# pcb.net
KiCad netlist of a schematic drawn in EAGLE
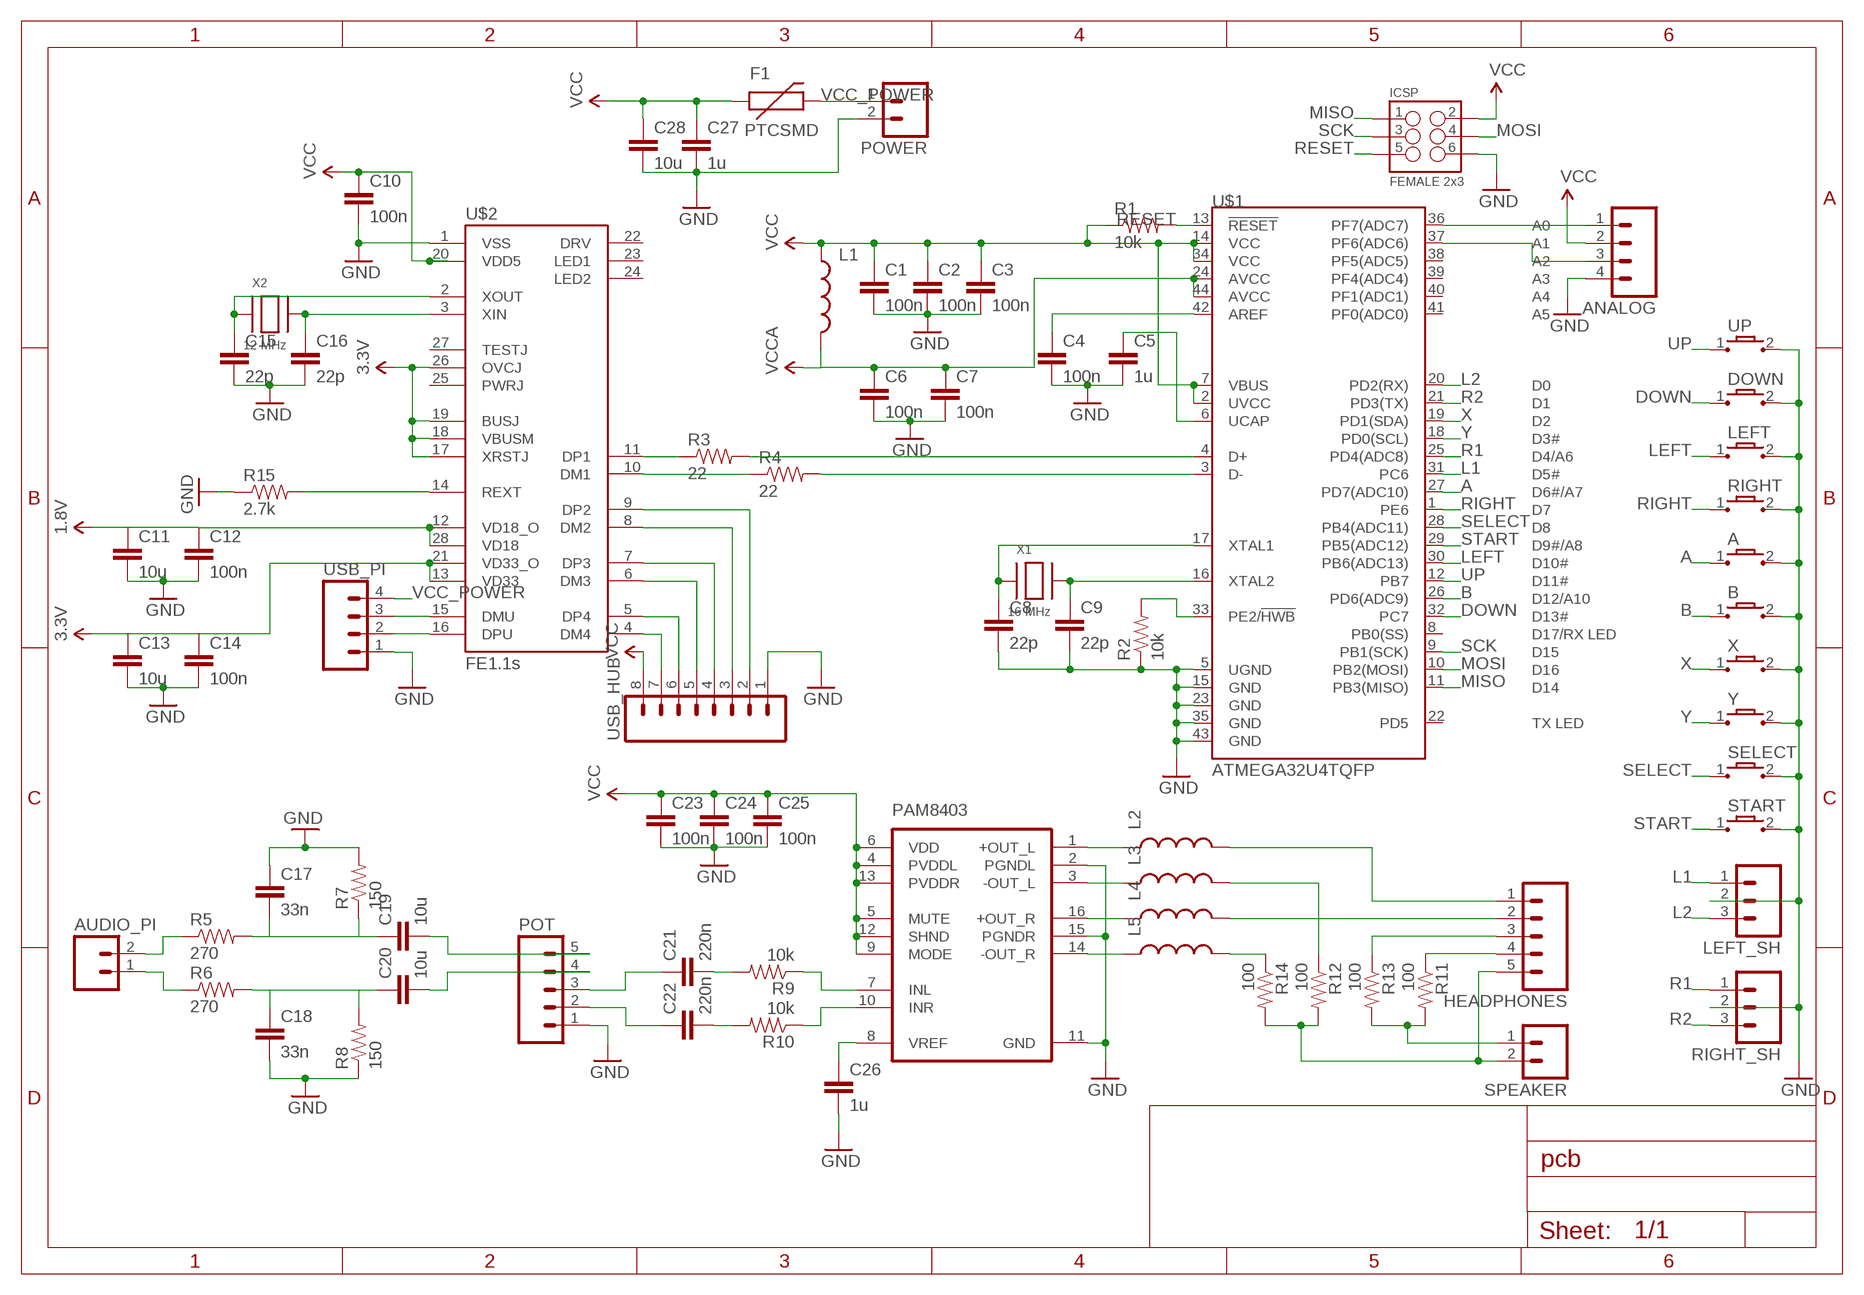
[diagram p0: schematic, sheet 1]

(export (version "E")
  (design (tool "Eeschema 10.0.6"))
  (components
    (comp (ref "A")
      (value "DMG_CONDUCTIVE")
      (footprint "eagle-import:CIRCLE_BUTTON2")
      (libsource (lib "eagle-import") (part "DMG_CONDUCTIVE"))
    )
    (comp (ref "ANALOG")
      (value "M04PTH")
      (footprint "eagle-import:1X04")
      (libsource (lib "eagle-import") (part "M04PTH"))
    )
    (comp (ref "AUDIO_PI")
      (value "M02PTH")
      (footprint "eagle-import:1X02")
      (libsource (lib "eagle-import") (part "M02PTH"))
    )
    (comp (ref "B")
      (value "DMG_CONDUCTIVE")
      (footprint "eagle-import:CIRCLE_BUTTON2")
      (libsource (lib "eagle-import") (part "DMG_CONDUCTIVE"))
    )
    (comp (ref "C1")
      (value "100n")
      (footprint "eagle-import:0805")
      (libsource (lib "eagle-import") (part "CAP0805"))
    )
    (comp (ref "C2")
      (value "100n")
      (footprint "eagle-import:0805")
      (libsource (lib "eagle-import") (part "CAP0805"))
    )
    (comp (ref "C3")
      (value "100n")
      (footprint "eagle-import:0805")
      (libsource (lib "eagle-import") (part "CAP0805"))
    )
    (comp (ref "C4")
      (value "100n")
      (footprint "eagle-import:0805")
      (libsource (lib "eagle-import") (part "CAP0805"))
    )
    (comp (ref "C5")
      (value "1u")
      (footprint "eagle-import:0805")
      (libsource (lib "eagle-import") (part "CAP0805"))
    )
    (comp (ref "C6")
      (value "100n")
      (footprint "eagle-import:0805")
      (libsource (lib "eagle-import") (part "CAP0805"))
    )
    (comp (ref "C7")
      (value "100n")
      (footprint "eagle-import:0805")
      (libsource (lib "eagle-import") (part "CAP0805"))
    )
    (comp (ref "C8")
      (value "22p")
      (footprint "eagle-import:0805")
      (libsource (lib "eagle-import") (part "CAP0805"))
    )
    (comp (ref "C9")
      (value "22p")
      (footprint "eagle-import:0805")
      (libsource (lib "eagle-import") (part "CAP0805"))
    )
    (comp (ref "C10")
      (value "100n")
      (footprint "eagle-import:0805")
      (libsource (lib "eagle-import") (part "CAP0805"))
    )
    (comp (ref "C11")
      (value "10u")
      (footprint "eagle-import:0805")
      (libsource (lib "eagle-import") (part "CAP0805"))
    )
    (comp (ref "C12")
      (value "100n")
      (footprint "eagle-import:0805")
      (libsource (lib "eagle-import") (part "CAP0805"))
    )
    (comp (ref "C13")
      (value "10u")
      (footprint "eagle-import:0805")
      (libsource (lib "eagle-import") (part "CAP0805"))
    )
    (comp (ref "C14")
      (value "100n")
      (footprint "eagle-import:0805")
      (libsource (lib "eagle-import") (part "CAP0805"))
    )
    (comp (ref "C15")
      (value "22p")
      (footprint "eagle-import:0805")
      (libsource (lib "eagle-import") (part "CAP0805"))
    )
    (comp (ref "C16")
      (value "22p")
      (footprint "eagle-import:0805")
      (libsource (lib "eagle-import") (part "CAP0805"))
    )
    (comp (ref "C17")
      (value "33n")
      (footprint "eagle-import:0805")
      (libsource (lib "eagle-import") (part "CAP0805"))
    )
    (comp (ref "C18")
      (value "33n")
      (footprint "eagle-import:0805")
      (libsource (lib "eagle-import") (part "CAP0805"))
    )
    (comp (ref "C19")
      (value "10u")
      (footprint "eagle-import:0805")
      (libsource (lib "eagle-import") (part "CAP0805"))
    )
    (comp (ref "C20")
      (value "10u")
      (footprint "eagle-import:0805")
      (libsource (lib "eagle-import") (part "CAP0805"))
    )
    (comp (ref "C21")
      (value "220n")
      (footprint "eagle-import:0805")
      (libsource (lib "eagle-import") (part "CAP0805"))
    )
    (comp (ref "C22")
      (value "220n")
      (footprint "eagle-import:0805")
      (libsource (lib "eagle-import") (part "CAP0805"))
    )
    (comp (ref "C23")
      (value "100n")
      (footprint "eagle-import:0805")
      (libsource (lib "eagle-import") (part "CAP0805"))
    )
    (comp (ref "C24")
      (value "100n")
      (footprint "eagle-import:0805")
      (libsource (lib "eagle-import") (part "CAP0805"))
    )
    (comp (ref "C25")
      (value "100n")
      (footprint "eagle-import:0805")
      (libsource (lib "eagle-import") (part "CAP0805"))
    )
    (comp (ref "C26")
      (value "1u")
      (footprint "eagle-import:0805")
      (libsource (lib "eagle-import") (part "CAP0805"))
    )
    (comp (ref "C27")
      (value "1u")
      (footprint "eagle-import:0805")
      (libsource (lib "eagle-import") (part "CAP0805"))
    )
    (comp (ref "C28")
      (value "10u")
      (footprint "eagle-import:0805")
      (libsource (lib "eagle-import") (part "CAP0805"))
    )
    (comp (ref "DOWN")
      (value "DMG_CONDUCTIVE")
      (footprint "eagle-import:CIRCLE_BUTTON2")
      (libsource (lib "eagle-import") (part "DMG_CONDUCTIVE"))
    )
    (comp (ref "F1")
      (value "PTCSMD")
      (footprint "eagle-import:PTC-1206")
      (libsource (lib "eagle-import") (part "PTCSMD"))
    )
    (comp (ref "HEADPHONES")
      (value "M05PTH")
      (footprint "eagle-import:1X05")
      (libsource (lib "eagle-import") (part "M05PTH"))
    )
    (comp (ref "ICSP")
      (value "FEMALE 2x3")
      (footprint "eagle-import:2X3")
      (libsource (lib "eagle-import") (part "M03X2FEMALE"))
    )
    (comp (ref "L1")
      (value "INDUCTOR0805")
      (footprint "eagle-import:0805")
      (libsource (lib "eagle-import") (part "INDUCTOR0805"))
    )
    (comp (ref "L2")
      (value "INDUCTOR0805")
      (footprint "eagle-import:0805")
      (libsource (lib "eagle-import") (part "INDUCTOR0805"))
    )
    (comp (ref "L3")
      (value "INDUCTOR0805")
      (footprint "eagle-import:0805")
      (libsource (lib "eagle-import") (part "INDUCTOR0805"))
    )
    (comp (ref "L4")
      (value "INDUCTOR0805")
      (footprint "eagle-import:0805")
      (libsource (lib "eagle-import") (part "INDUCTOR0805"))
    )
    (comp (ref "L5")
      (value "INDUCTOR0805")
      (footprint "eagle-import:0805")
      (libsource (lib "eagle-import") (part "INDUCTOR0805"))
    )
    (comp (ref "LEFT")
      (value "DMG_CONDUCTIVE")
      (footprint "eagle-import:CIRCLE_BUTTON2")
      (libsource (lib "eagle-import") (part "DMG_CONDUCTIVE"))
    )
    (comp (ref "LEFT_SH")
      (value "M03PTH")
      (footprint "eagle-import:1X03")
      (libsource (lib "eagle-import") (part "M03PTH"))
    )
    (comp (ref "PAM8403")
      (value "PAM8403")
      (footprint "eagle-import:SOP-16")
      (libsource (lib "eagle-import") (part "PAM8403"))
    )
    (comp (ref "POT")
      (value "M05PTH")
      (footprint "eagle-import:1X05")
      (libsource (lib "eagle-import") (part "M05PTH"))
    )
    (comp (ref "POWER")
      (value "M02PTH")
      (footprint "eagle-import:1X02")
      (libsource (lib "eagle-import") (part "M02PTH"))
    )
    (comp (ref "R1")
      (value "10k")
      (footprint "eagle-import:0805")
      (libsource (lib "eagle-import") (part "RESISTOR0805-RES"))
    )
    (comp (ref "R2")
      (value "10k")
      (footprint "eagle-import:0805")
      (libsource (lib "eagle-import") (part "RESISTOR0805-RES"))
    )
    (comp (ref "R3")
      (value "22")
      (footprint "eagle-import:0805")
      (libsource (lib "eagle-import") (part "RESISTOR0805-RES"))
    )
    (comp (ref "R4")
      (value "22")
      (footprint "eagle-import:0805")
      (libsource (lib "eagle-import") (part "RESISTOR0805-RES"))
    )
    (comp (ref "R5")
      (value "270")
      (footprint "eagle-import:0805")
      (libsource (lib "eagle-import") (part "RESISTOR0805-RES"))
    )
    (comp (ref "R6")
      (value "270")
      (footprint "eagle-import:0805")
      (libsource (lib "eagle-import") (part "RESISTOR0805-RES"))
    )
    (comp (ref "R7")
      (value "150")
      (footprint "eagle-import:0805")
      (libsource (lib "eagle-import") (part "RESISTOR0805-RES"))
    )
    (comp (ref "R8")
      (value "150")
      (footprint "eagle-import:0805")
      (libsource (lib "eagle-import") (part "RESISTOR0805-RES"))
    )
    (comp (ref "R9")
      (value "10k")
      (footprint "eagle-import:0805")
      (libsource (lib "eagle-import") (part "RESISTOR0805-RES"))
    )
    (comp (ref "R10")
      (value "10k")
      (footprint "eagle-import:0805")
      (libsource (lib "eagle-import") (part "RESISTOR0805-RES"))
    )
    (comp (ref "R11")
      (value "100")
      (footprint "eagle-import:0805")
      (libsource (lib "eagle-import") (part "RESISTOR0805-RES"))
    )
    (comp (ref "R12")
      (value "100")
      (footprint "eagle-import:0805")
      (libsource (lib "eagle-import") (part "RESISTOR0805-RES"))
    )
    (comp (ref "R13")
      (value "100")
      (footprint "eagle-import:0805")
      (libsource (lib "eagle-import") (part "RESISTOR0805-RES"))
    )
    (comp (ref "R14")
      (value "100")
      (footprint "eagle-import:0805")
      (libsource (lib "eagle-import") (part "RESISTOR0805-RES"))
    )
    (comp (ref "R15")
      (value "2.7k")
      (footprint "eagle-import:0805")
      (libsource (lib "eagle-import") (part "RESISTOR0805-RES"))
    )
    (comp (ref "RIGHT")
      (value "DMG_CONDUCTIVE")
      (footprint "eagle-import:CIRCLE_BUTTON2")
      (libsource (lib "eagle-import") (part "DMG_CONDUCTIVE"))
    )
    (comp (ref "RIGHT_SH")
      (value "M03PTH")
      (footprint "eagle-import:1X03")
      (libsource (lib "eagle-import") (part "M03PTH"))
    )
    (comp (ref "SELECT")
      (value "DMG_CONDUCTIVE2")
      (footprint "eagle-import:START_STOP2")
      (libsource (lib "eagle-import") (part "DMG_CONDUCTIVE2"))
    )
    (comp (ref "SPEAKER")
      (value "M02PTH")
      (footprint "eagle-import:1X02")
      (libsource (lib "eagle-import") (part "M02PTH"))
    )
    (comp (ref "START")
      (value "DMG_CONDUCTIVE2")
      (footprint "eagle-import:START_STOP2")
      (libsource (lib "eagle-import") (part "DMG_CONDUCTIVE2"))
    )
    (comp (ref "U$1")
      (value "ATMEGA32U4TQFP")
      (footprint "eagle-import:SPARKFUN-DIGITALIC_TQFP44")
      (libsource (lib "eagle-import") (part "ATMEGA32U4TQFP"))
    )
    (comp (ref "U$2")
      (value "FE1.1S")
      (footprint "eagle-import:FE1.1S_SSOP-28")
      (libsource (lib "eagle-import") (part "FE1.1S"))
    )
    (comp (ref "UP")
      (value "DMG_CONDUCTIVE")
      (footprint "eagle-import:CIRCLE_BUTTON2")
      (libsource (lib "eagle-import") (part "DMG_CONDUCTIVE"))
    )
    (comp (ref "USB_HUB")
      (value "M08")
      (footprint "eagle-import:1X08_ROUND")
      (libsource (lib "eagle-import") (part "M08"))
    )
    (comp (ref "USB_PI")
      (value "M04PTH")
      (footprint "eagle-import:1X04")
      (libsource (lib "eagle-import") (part "M04PTH"))
    )
    (comp (ref "X")
      (value "DMG_CONDUCTIVE")
      (footprint "eagle-import:CIRCLE_BUTTON2")
      (libsource (lib "eagle-import") (part "DMG_CONDUCTIVE"))
    )
    (comp (ref "X1")
      (value "16 MHz")
      (footprint "eagle-import:NX5032")
      (libsource (lib "eagle-import") (part "XTALNX5032"))
    )
    (comp (ref "X2")
      (value "12 MHz")
      (footprint "eagle-import:NX5032")
      (libsource (lib "eagle-import") (part "XTALNX5032"))
    )
    (comp (ref "Y")
      (value "DMG_CONDUCTIVE")
      (footprint "eagle-import:CIRCLE_BUTTON2")
      (libsource (lib "eagle-import") (part "DMG_CONDUCTIVE"))
    )
  )
  (nets
    (net (code "1") (name "/A") (class "Default")
      (node (ref "A") (pin "1") (pinfunction "1_1") (pintype "passive"))
      (node (ref "U$1") (pin "27") (pinfunction "PD7(ADC10)_27") (pintype "bidirectional"))
    )
    (net (code "2") (name "/B") (class "Default")
      (node (ref "B") (pin "1") (pinfunction "1_1") (pintype "passive"))
      (node (ref "U$1") (pin "26") (pinfunction "PD6(ADC9)_26") (pintype "bidirectional"))
    )
    (net (code "3") (name "/DOWN") (class "Default")
      (node (ref "DOWN") (pin "1") (pinfunction "1_1") (pintype "passive"))
      (node (ref "U$1") (pin "32") (pinfunction "PC7_32") (pintype "bidirectional"))
    )
    (net (code "4") (name "/L1") (class "Default")
      (node (ref "LEFT_SH") (pin "1") (pinfunction "1_1") (pintype "passive"))
      (node (ref "U$1") (pin "31") (pinfunction "PC6_31") (pintype "bidirectional"))
    )
    (net (code "5") (name "/L2") (class "Default")
      (node (ref "LEFT_SH") (pin "3") (pinfunction "3_3") (pintype "passive"))
      (node (ref "U$1") (pin "20") (pinfunction "PD2(RX)_20") (pintype "bidirectional"))
    )
    (net (code "6") (name "/LEFT") (class "Default")
      (node (ref "LEFT") (pin "1") (pinfunction "1_1") (pintype "passive"))
      (node (ref "U$1") (pin "30") (pinfunction "PB6(ADC13)_30") (pintype "bidirectional"))
    )
    (net (code "7") (name "/MISO") (class "Default")
      (node (ref "ICSP") (pin "1") (pinfunction "1_1") (pintype "bidirectional"))
      (node (ref "U$1") (pin "11") (pinfunction "PB3(MISO)_11") (pintype "bidirectional"))
    )
    (net (code "8") (name "/MOSI") (class "Default")
      (node (ref "ICSP") (pin "4") (pinfunction "4_4") (pintype "bidirectional"))
      (node (ref "U$1") (pin "10") (pinfunction "PB2(MOSI)_10") (pintype "bidirectional"))
    )
    (net (code "9") (name "/R1") (class "Default")
      (node (ref "RIGHT_SH") (pin "1") (pinfunction "1_1") (pintype "passive"))
      (node (ref "U$1") (pin "25") (pinfunction "PD4(ADC8)_25") (pintype "bidirectional"))
    )
    (net (code "10") (name "/R2") (class "Default")
      (node (ref "RIGHT_SH") (pin "3") (pinfunction "3_3") (pintype "passive"))
      (node (ref "U$1") (pin "21") (pinfunction "PD3(TX)_21") (pintype "bidirectional"))
    )
    (net (code "11") (name "/RESET") (class "Default")
      (node (ref "ICSP") (pin "5") (pinfunction "5_5") (pintype "bidirectional"))
      (node (ref "R1") (pin "2") (pinfunction "2_2") (pintype "passive"))
      (node (ref "U$1") (pin "13") (pinfunction "~{RESET}_13") (pintype "bidirectional"))
    )
    (net (code "12") (name "/RIGHT") (class "Default")
      (node (ref "RIGHT") (pin "1") (pinfunction "1_1") (pintype "passive"))
      (node (ref "U$1") (pin "1") (pinfunction "PE6_1") (pintype "bidirectional"))
    )
    (net (code "13") (name "/SCK") (class "Default")
      (node (ref "ICSP") (pin "3") (pinfunction "3_3") (pintype "bidirectional"))
      (node (ref "U$1") (pin "9") (pinfunction "PB1(SCK)_9") (pintype "bidirectional"))
    )
    (net (code "14") (name "/SELECT") (class "Default")
      (node (ref "SELECT") (pin "1") (pinfunction "1_1") (pintype "passive"))
      (node (ref "U$1") (pin "28") (pinfunction "PB4(ADC11)_28") (pintype "bidirectional"))
    )
    (net (code "15") (name "/START") (class "Default")
      (node (ref "START") (pin "1") (pinfunction "1_1") (pintype "passive"))
      (node (ref "U$1") (pin "29") (pinfunction "PB5(ADC12)_29") (pintype "bidirectional"))
    )
    (net (code "16") (name "/UP") (class "Default")
      (node (ref "U$1") (pin "12") (pinfunction "PB7_12") (pintype "bidirectional"))
      (node (ref "UP") (pin "1") (pinfunction "1_1") (pintype "passive"))
    )
    (net (code "17") (name "/VCC_POWER") (class "Default")
      (node (ref "F1") (pin "2") (pinfunction "2_2") (pintype "bidirectional"))
      (node (ref "POWER") (pin "1") (pinfunction "1_1") (pintype "passive"))
      (node (ref "USB_PI") (pin "4") (pinfunction "4_4") (pintype "passive"))
    )
    (net (code "18") (name "/X") (class "Default")
      (node (ref "U$1") (pin "19") (pinfunction "PD1(SDA)_19") (pintype "bidirectional"))
      (node (ref "X") (pin "1") (pinfunction "1_1") (pintype "passive"))
    )
    (net (code "19") (name "/Y") (class "Default")
      (node (ref "U$1") (pin "18") (pinfunction "PD0(SCL)_18") (pintype "bidirectional"))
      (node (ref "Y") (pin "1") (pinfunction "1_1") (pintype "passive"))
    )
    (net (code "20") (name "1.8V") (class "Default")
      (node (ref "C11") (pin "1") (pinfunction "1_1") (pintype "passive"))
      (node (ref "C12") (pin "1") (pinfunction "1_1") (pintype "passive"))
      (node (ref "U$2") (pin "12") (pinfunction "VD18_O_12") (pintype "bidirectional"))
      (node (ref "U$2") (pin "28") (pinfunction "VD18_28") (pintype "bidirectional"))
    )
    (net (code "21") (name "3.3V") (class "Default")
      (node (ref "C13") (pin "1") (pinfunction "1_1") (pintype "passive"))
      (node (ref "C14") (pin "1") (pinfunction "1_1") (pintype "passive"))
      (node (ref "U$2") (pin "13") (pinfunction "VD33_13") (pintype "bidirectional"))
      (node (ref "U$2") (pin "17") (pinfunction "XRSTJ_17") (pintype "bidirectional"))
      (node (ref "U$2") (pin "18") (pinfunction "VBUSM_18") (pintype "bidirectional"))
      (node (ref "U$2") (pin "19") (pinfunction "BUSJ_19") (pintype "bidirectional"))
      (node (ref "U$2") (pin "21") (pinfunction "VD33_O_21") (pintype "bidirectional"))
      (node (ref "U$2") (pin "26") (pinfunction "OVCJ_26") (pintype "bidirectional"))
    )
    (net (code "22") (name "GND") (class "Default")
      (node (ref "A") (pin "2") (pinfunction "2_2") (pintype "passive"))
      (node (ref "ANALOG") (pin "4") (pinfunction "4_4") (pintype "passive"))
      (node (ref "B") (pin "2") (pinfunction "2_2") (pintype "passive"))
      (node (ref "C1") (pin "2") (pinfunction "2_2") (pintype "passive"))
      (node (ref "C10") (pin "2") (pinfunction "2_2") (pintype "passive"))
      (node (ref "C11") (pin "2") (pinfunction "2_2") (pintype "passive"))
      (node (ref "C12") (pin "2") (pinfunction "2_2") (pintype "passive"))
      (node (ref "C13") (pin "2") (pinfunction "2_2") (pintype "passive"))
      (node (ref "C14") (pin "2") (pinfunction "2_2") (pintype "passive"))
      (node (ref "C15") (pin "2") (pinfunction "2_2") (pintype "passive"))
      (node (ref "C16") (pin "2") (pinfunction "2_2") (pintype "passive"))
      (node (ref "C17") (pin "1") (pinfunction "1_1") (pintype "passive"))
      (node (ref "C18") (pin "2") (pinfunction "2_2") (pintype "passive"))
      (node (ref "C2") (pin "2") (pinfunction "2_2") (pintype "passive"))
      (node (ref "C23") (pin "2") (pinfunction "2_2") (pintype "passive"))
      (node (ref "C24") (pin "2") (pinfunction "2_2") (pintype "passive"))
      (node (ref "C25") (pin "2") (pinfunction "2_2") (pintype "passive"))
      (node (ref "C26") (pin "2") (pinfunction "2_2") (pintype "passive"))
      (node (ref "C27") (pin "2") (pinfunction "2_2") (pintype "passive"))
      (node (ref "C28") (pin "2") (pinfunction "2_2") (pintype "passive"))
      (node (ref "C3") (pin "2") (pinfunction "2_2") (pintype "passive"))
      (node (ref "C4") (pin "2") (pinfunction "2_2") (pintype "passive"))
      (node (ref "C5") (pin "2") (pinfunction "2_2") (pintype "passive"))
      (node (ref "C6") (pin "2") (pinfunction "2_2") (pintype "passive"))
      (node (ref "C7") (pin "2") (pinfunction "2_2") (pintype "passive"))
      (node (ref "C8") (pin "2") (pinfunction "2_2") (pintype "passive"))
      (node (ref "C9") (pin "2") (pinfunction "2_2") (pintype "passive"))
      (node (ref "DOWN") (pin "2") (pinfunction "2_2") (pintype "passive"))
      (node (ref "ICSP") (pin "6") (pinfunction "6_6") (pintype "bidirectional"))
      (node (ref "LEFT") (pin "2") (pinfunction "2_2") (pintype "passive"))
      (node (ref "LEFT_SH") (pin "2") (pinfunction "2_2") (pintype "passive"))
      (node (ref "PAM8403") (pin "11") (pinfunction "GND_11") (pintype "output"))
      (node (ref "PAM8403") (pin "15") (pinfunction "PGNDR_15") (pintype "output"))
      (node (ref "PAM8403") (pin "2") (pinfunction "PGNDL_2") (pintype "input"))
      (node (ref "POT") (pin "1") (pinfunction "1_1") (pintype "passive"))
      (node (ref "POWER") (pin "2") (pinfunction "2_2") (pintype "passive"))
      (node (ref "R15") (pin "1") (pinfunction "1_1") (pintype "passive"))
      (node (ref "R2") (pin "1") (pinfunction "1_1") (pintype "passive"))
      (node (ref "R7") (pin "2") (pinfunction "2_2") (pintype "passive"))
      (node (ref "R8") (pin "1") (pinfunction "1_1") (pintype "passive"))
      (node (ref "RIGHT") (pin "2") (pinfunction "2_2") (pintype "passive"))
      (node (ref "RIGHT_SH") (pin "2") (pinfunction "2_2") (pintype "passive"))
      (node (ref "SELECT") (pin "2") (pinfunction "2_2") (pintype "passive"))
      (node (ref "START") (pin "2") (pinfunction "2_2") (pintype "passive"))
      (node (ref "U$1") (pin "15") (pinfunction "GND_15") (pintype "bidirectional"))
      (node (ref "U$1") (pin "23") (pinfunction "GND_23") (pintype "bidirectional"))
      (node (ref "U$1") (pin "35") (pinfunction "GND_35") (pintype "bidirectional"))
      (node (ref "U$1") (pin "43") (pinfunction "GND_43") (pintype "bidirectional"))
      (node (ref "U$1") (pin "5") (pinfunction "UGND_5") (pintype "bidirectional"))
      (node (ref "U$2") (pin "1") (pinfunction "VSS_1") (pintype "bidirectional"))
      (node (ref "UP") (pin "2") (pinfunction "2_2") (pintype "passive"))
      (node (ref "USB_HUB") (pin "1") (pinfunction "1_1") (pintype "passive"))
      (node (ref "USB_PI") (pin "1") (pinfunction "1_1") (pintype "passive"))
      (node (ref "X") (pin "2") (pinfunction "2_2") (pintype "passive"))
      (node (ref "Y") (pin "2") (pinfunction "2_2") (pintype "passive"))
    )
    (net (code "23") (name "Net-(AUDIO_PI-Pad1)") (class "Default")
      (node (ref "AUDIO_PI") (pin "1") (pinfunction "1_1") (pintype "passive"))
      (node (ref "R6") (pin "1") (pinfunction "1_1") (pintype "passive"))
    )
    (net (code "24") (name "Net-(AUDIO_PI-Pad2)") (class "Default")
      (node (ref "AUDIO_PI") (pin "2") (pinfunction "2_2") (pintype "passive"))
      (node (ref "R5") (pin "1") (pinfunction "1_1") (pintype "passive"))
    )
    (net (code "25") (name "Net-(C17-Pad2)") (class "Default")
      (node (ref "C17") (pin "2") (pinfunction "2_2") (pintype "passive"))
      (node (ref "C19") (pin "1") (pinfunction "1_1") (pintype "passive"))
      (node (ref "R5") (pin "2") (pinfunction "2_2") (pintype "passive"))
      (node (ref "R7") (pin "1") (pinfunction "1_1") (pintype "passive"))
    )
    (net (code "26") (name "Net-(C18-Pad1)") (class "Default")
      (node (ref "C18") (pin "1") (pinfunction "1_1") (pintype "passive"))
      (node (ref "C20") (pin "1") (pinfunction "1_1") (pintype "passive"))
      (node (ref "R6") (pin "2") (pinfunction "2_2") (pintype "passive"))
      (node (ref "R8") (pin "2") (pinfunction "2_2") (pintype "passive"))
    )
    (net (code "27") (name "Net-(C19-Pad2)") (class "Default")
      (node (ref "C19") (pin "2") (pinfunction "2_2") (pintype "passive"))
      (node (ref "POT") (pin "5") (pinfunction "5_5") (pintype "passive"))
    )
    (net (code "28") (name "Net-(C20-Pad2)") (class "Default")
      (node (ref "C20") (pin "2") (pinfunction "2_2") (pintype "passive"))
      (node (ref "POT") (pin "4") (pinfunction "4_4") (pintype "passive"))
    )
    (net (code "29") (name "Net-(C21-Pad1)") (class "Default")
      (node (ref "C21") (pin "1") (pinfunction "1_1") (pintype "passive"))
      (node (ref "POT") (pin "3") (pinfunction "3_3") (pintype "passive"))
    )
    (net (code "30") (name "Net-(C21-Pad2)") (class "Default")
      (node (ref "C21") (pin "2") (pinfunction "2_2") (pintype "passive"))
      (node (ref "R9") (pin "2") (pinfunction "2_2") (pintype "passive"))
    )
    (net (code "31") (name "Net-(C22-Pad1)") (class "Default")
      (node (ref "C22") (pin "1") (pinfunction "1_1") (pintype "passive"))
      (node (ref "POT") (pin "2") (pinfunction "2_2") (pintype "passive"))
    )
    (net (code "32") (name "Net-(C22-Pad2)") (class "Default")
      (node (ref "C22") (pin "2") (pinfunction "2_2") (pintype "passive"))
      (node (ref "R10") (pin "2") (pinfunction "2_2") (pintype "passive"))
    )
    (net (code "33") (name "Net-(HEADPHONES-Pad1)") (class "Default")
      (node (ref "HEADPHONES") (pin "1") (pinfunction "1_1") (pintype "passive"))
      (node (ref "L2") (pin "2") (pinfunction "2_2") (pintype "passive"))
    )
    (net (code "34") (name "Net-(HEADPHONES-Pad2)") (class "Default")
      (node (ref "HEADPHONES") (pin "2") (pinfunction "2_2") (pintype "passive"))
      (node (ref "L4") (pin "2") (pinfunction "2_2") (pintype "passive"))
    )
    (net (code "35") (name "Net-(HEADPHONES-Pad3)") (class "Default")
      (node (ref "HEADPHONES") (pin "3") (pinfunction "3_3") (pintype "passive"))
      (node (ref "R13") (pin "1") (pinfunction "1_1") (pintype "passive"))
    )
    (net (code "36") (name "Net-(HEADPHONES-Pad4)") (class "Default")
      (node (ref "HEADPHONES") (pin "4") (pinfunction "4_4") (pintype "passive"))
      (node (ref "R11") (pin "1") (pinfunction "1_1") (pintype "passive"))
    )
    (net (code "37") (name "Net-(HEADPHONES-Pad5)") (class "Default")
      (node (ref "HEADPHONES") (pin "5") (pinfunction "5_5") (pintype "passive"))
      (node (ref "R12") (pin "2") (pinfunction "2_2") (pintype "passive"))
      (node (ref "R14") (pin "2") (pinfunction "2_2") (pintype "passive"))
      (node (ref "SPEAKER") (pin "2") (pinfunction "2_2") (pintype "passive"))
    )
    (net (code "38") (name "Net-(L3-Pad2)") (class "Default")
      (node (ref "L3") (pin "2") (pinfunction "2_2") (pintype "passive"))
      (node (ref "R12") (pin "1") (pinfunction "1_1") (pintype "passive"))
    )
    (net (code "39") (name "Net-(L5-Pad2)") (class "Default")
      (node (ref "L5") (pin "2") (pinfunction "2_2") (pintype "passive"))
      (node (ref "R14") (pin "1") (pinfunction "1_1") (pintype "passive"))
    )
    (net (code "40") (name "Net-(PAM8403-+OUT_L)") (class "Default")
      (node (ref "L2") (pin "1") (pinfunction "1_1") (pintype "passive"))
      (node (ref "PAM8403") (pin "1") (pinfunction "+OUT_L_1") (pintype "input"))
    )
    (net (code "41") (name "Net-(PAM8403-+OUT_R)") (class "Default")
      (node (ref "L4") (pin "1") (pinfunction "1_1") (pintype "passive"))
      (node (ref "PAM8403") (pin "16") (pinfunction "+OUT_R_16") (pintype "output"))
    )
    (net (code "42") (name "Net-(PAM8403--OUT_L)") (class "Default")
      (node (ref "L3") (pin "1") (pinfunction "1_1") (pintype "passive"))
      (node (ref "PAM8403") (pin "3") (pinfunction "-OUT_L_3") (pintype "input"))
    )
    (net (code "43") (name "Net-(PAM8403--OUT_R)") (class "Default")
      (node (ref "L5") (pin "1") (pinfunction "1_1") (pintype "passive"))
      (node (ref "PAM8403") (pin "14") (pinfunction "-OUT_R_14") (pintype "output"))
    )
    (net (code "44") (name "Net-(PAM8403-INL)") (class "Default")
      (node (ref "PAM8403") (pin "7") (pinfunction "INL_7") (pintype "input"))
      (node (ref "R9") (pin "1") (pinfunction "1_1") (pintype "passive"))
    )
    (net (code "45") (name "Net-(PAM8403-INR)") (class "Default")
      (node (ref "PAM8403") (pin "10") (pinfunction "INR_10") (pintype "output"))
      (node (ref "R10") (pin "1") (pinfunction "1_1") (pintype "passive"))
    )
    (net (code "46") (name "Net-(PAM8403-VREF)") (class "Default")
      (node (ref "C26") (pin "1") (pinfunction "1_1") (pintype "passive"))
      (node (ref "PAM8403") (pin "8") (pinfunction "VREF_8") (pintype "input"))
    )
    (net (code "47") (name "Net-(R11-Pad2)") (class "Default")
      (node (ref "R11") (pin "2") (pinfunction "2_2") (pintype "passive"))
      (node (ref "R13") (pin "2") (pinfunction "2_2") (pintype "passive"))
      (node (ref "SPEAKER") (pin "1") (pinfunction "1_1") (pintype "passive"))
    )
    (net (code "48") (name "Net-(U$1-AREF)") (class "Default")
      (node (ref "C4") (pin "1") (pinfunction "1_1") (pintype "passive"))
      (node (ref "U$1") (pin "42") (pinfunction "AREF_42") (pintype "bidirectional"))
    )
    (net (code "49") (name "Net-(U$1-D+)") (class "Default")
      (node (ref "R3") (pin "2") (pinfunction "2_2") (pintype "passive"))
      (node (ref "U$1") (pin "4") (pinfunction "D+_4") (pintype "bidirectional"))
    )
    (net (code "50") (name "Net-(U$1-D-)") (class "Default")
      (node (ref "R4") (pin "2") (pinfunction "2_2") (pintype "passive"))
      (node (ref "U$1") (pin "3") (pinfunction "D-_3") (pintype "bidirectional"))
    )
    (net (code "51") (name "Net-(U$1-PE2{slash}~{HWB})") (class "Default")
      (node (ref "R2") (pin "2") (pinfunction "2_2") (pintype "passive"))
      (node (ref "U$1") (pin "33") (pinfunction "PE2/~{HWB}_33") (pintype "bidirectional"))
    )
    (net (code "52") (name "Net-(U$1-PF6(ADC6))") (class "Default")
      (node (ref "ANALOG") (pin "3") (pinfunction "3_3") (pintype "passive"))
      (node (ref "U$1") (pin "37") (pinfunction "PF6(ADC6)_37") (pintype "bidirectional"))
    )
    (net (code "53") (name "Net-(U$1-PF7(ADC7))") (class "Default")
      (node (ref "ANALOG") (pin "1") (pinfunction "1_1") (pintype "passive"))
      (node (ref "U$1") (pin "36") (pinfunction "PF7(ADC7)_36") (pintype "bidirectional"))
    )
    (net (code "54") (name "Net-(U$1-UCAP)") (class "Default")
      (node (ref "C5") (pin "1") (pinfunction "1_1") (pintype "passive"))
      (node (ref "U$1") (pin "6") (pinfunction "UCAP_6") (pintype "bidirectional"))
    )
    (net (code "55") (name "Net-(U$1-XTAL1)") (class "Default")
      (node (ref "C8") (pin "1") (pinfunction "1_1") (pintype "passive"))
      (node (ref "U$1") (pin "17") (pinfunction "XTAL1_17") (pintype "bidirectional"))
      (node (ref "X1") (pin "P$1") (pinfunction "P$1_P$1") (pintype "bidirectional"))
    )
    (net (code "56") (name "Net-(U$1-XTAL2)") (class "Default")
      (node (ref "C9") (pin "1") (pinfunction "1_1") (pintype "passive"))
      (node (ref "U$1") (pin "16") (pinfunction "XTAL2_16") (pintype "bidirectional"))
      (node (ref "X1") (pin "P$2") (pinfunction "P$2_P$2") (pintype "bidirectional"))
    )
    (net (code "57") (name "Net-(U$2-DM1)") (class "Default")
      (node (ref "R4") (pin "1") (pinfunction "1_1") (pintype "passive"))
      (node (ref "U$2") (pin "10") (pinfunction "DM1_10") (pintype "bidirectional"))
    )
    (net (code "58") (name "Net-(U$2-DM2)") (class "Default")
      (node (ref "U$2") (pin "8") (pinfunction "DM2_8") (pintype "bidirectional"))
      (node (ref "USB_HUB") (pin "3") (pinfunction "3_3") (pintype "passive"))
    )
    (net (code "59") (name "Net-(U$2-DM3)") (class "Default")
      (node (ref "U$2") (pin "6") (pinfunction "DM3_6") (pintype "bidirectional"))
      (node (ref "USB_HUB") (pin "5") (pinfunction "5_5") (pintype "passive"))
    )
    (net (code "60") (name "Net-(U$2-DM4)") (class "Default")
      (node (ref "U$2") (pin "4") (pinfunction "DM4_4") (pintype "bidirectional"))
      (node (ref "USB_HUB") (pin "7") (pinfunction "7_7") (pintype "passive"))
    )
    (net (code "61") (name "Net-(U$2-DMU)") (class "Default")
      (node (ref "U$2") (pin "15") (pinfunction "DMU_15") (pintype "bidirectional"))
      (node (ref "USB_PI") (pin "3") (pinfunction "3_3") (pintype "passive"))
    )
    (net (code "62") (name "Net-(U$2-DP1)") (class "Default")
      (node (ref "R3") (pin "1") (pinfunction "1_1") (pintype "passive"))
      (node (ref "U$2") (pin "11") (pinfunction "DP1_11") (pintype "bidirectional"))
    )
    (net (code "63") (name "Net-(U$2-DP2)") (class "Default")
      (node (ref "U$2") (pin "9") (pinfunction "DP2_9") (pintype "bidirectional"))
      (node (ref "USB_HUB") (pin "2") (pinfunction "2_2") (pintype "passive"))
    )
    (net (code "64") (name "Net-(U$2-DP3)") (class "Default")
      (node (ref "U$2") (pin "7") (pinfunction "DP3_7") (pintype "bidirectional"))
      (node (ref "USB_HUB") (pin "4") (pinfunction "4_4") (pintype "passive"))
    )
    (net (code "65") (name "Net-(U$2-DP4)") (class "Default")
      (node (ref "U$2") (pin "5") (pinfunction "DP4_5") (pintype "bidirectional"))
      (node (ref "USB_HUB") (pin "6") (pinfunction "6_6") (pintype "passive"))
    )
    (net (code "66") (name "Net-(U$2-DPU)") (class "Default")
      (node (ref "U$2") (pin "16") (pinfunction "DPU_16") (pintype "bidirectional"))
      (node (ref "USB_PI") (pin "2") (pinfunction "2_2") (pintype "passive"))
    )
    (net (code "67") (name "Net-(U$2-REXT)") (class "Default")
      (node (ref "R15") (pin "2") (pinfunction "2_2") (pintype "passive"))
      (node (ref "U$2") (pin "14") (pinfunction "REXT_14") (pintype "bidirectional"))
    )
    (net (code "68") (name "Net-(U$2-XIN)") (class "Default")
      (node (ref "C16") (pin "1") (pinfunction "1_1") (pintype "passive"))
      (node (ref "U$2") (pin "3") (pinfunction "XIN_3") (pintype "bidirectional"))
      (node (ref "X2") (pin "P$2") (pinfunction "P$2_P$2") (pintype "bidirectional"))
    )
    (net (code "69") (name "Net-(U$2-XOUT)") (class "Default")
      (node (ref "C15") (pin "1") (pinfunction "1_1") (pintype "passive"))
      (node (ref "U$2") (pin "2") (pinfunction "XOUT_2") (pintype "bidirectional"))
      (node (ref "X2") (pin "P$1") (pinfunction "P$1_P$1") (pintype "bidirectional"))
    )
    (net (code "70") (name "VCC") (class "Default")
      (node (ref "ANALOG") (pin "2") (pinfunction "2_2") (pintype "passive"))
      (node (ref "C1") (pin "1") (pinfunction "1_1") (pintype "passive"))
      (node (ref "C10") (pin "1") (pinfunction "1_1") (pintype "passive"))
      (node (ref "C2") (pin "1") (pinfunction "1_1") (pintype "passive"))
      (node (ref "C23") (pin "1") (pinfunction "1_1") (pintype "passive"))
      (node (ref "C24") (pin "1") (pinfunction "1_1") (pintype "passive"))
      (node (ref "C25") (pin "1") (pinfunction "1_1") (pintype "passive"))
      (node (ref "C27") (pin "1") (pinfunction "1_1") (pintype "passive"))
      (node (ref "C28") (pin "1") (pinfunction "1_1") (pintype "passive"))
      (node (ref "C3") (pin "1") (pinfunction "1_1") (pintype "passive"))
      (node (ref "F1") (pin "1") (pinfunction "1_1") (pintype "bidirectional"))
      (node (ref "ICSP") (pin "2") (pinfunction "2_2") (pintype "bidirectional"))
      (node (ref "L1") (pin "1") (pinfunction "1_1") (pintype "passive"))
      (node (ref "PAM8403") (pin "12") (pinfunction "SHND_12") (pintype "output"))
      (node (ref "PAM8403") (pin "13") (pinfunction "PVDDR_13") (pintype "output"))
      (node (ref "PAM8403") (pin "4") (pinfunction "PVDDL_4") (pintype "input"))
      (node (ref "PAM8403") (pin "5") (pinfunction "MUTE_5") (pintype "input"))
      (node (ref "PAM8403") (pin "6") (pinfunction "VDD_6") (pintype "input"))
      (node (ref "PAM8403") (pin "9") (pinfunction "MODE_9") (pintype "output"))
      (node (ref "R1") (pin "1") (pinfunction "1_1") (pintype "passive"))
      (node (ref "U$1") (pin "14") (pinfunction "VCC_14") (pintype "bidirectional"))
      (node (ref "U$1") (pin "2") (pinfunction "UVCC_2") (pintype "bidirectional"))
      (node (ref "U$1") (pin "34") (pinfunction "VCC_34") (pintype "bidirectional"))
      (node (ref "U$1") (pin "7") (pinfunction "VBUS_7") (pintype "bidirectional"))
      (node (ref "U$2") (pin "20") (pinfunction "VDD5_20") (pintype "bidirectional"))
      (node (ref "USB_HUB") (pin "8") (pinfunction "8_8") (pintype "passive"))
    )
    (net (code "71") (name "VCCA") (class "Default")
      (node (ref "C6") (pin "1") (pinfunction "1_1") (pintype "passive"))
      (node (ref "C7") (pin "1") (pinfunction "1_1") (pintype "passive"))
      (node (ref "L1") (pin "2") (pinfunction "2_2") (pintype "passive"))
      (node (ref "U$1") (pin "24") (pinfunction "AVCC_24") (pintype "bidirectional"))
      (node (ref "U$1") (pin "44") (pinfunction "AVCC_44") (pintype "bidirectional"))
    )
    (net (code "72") (name "unconnected-(U$1-PB0(SS)-Pad8)") (class "Default")
      (node (ref "U$1") (pin "8") (pinfunction "PB0(SS)_8") (pintype "bidirectional"))
    )
    (net (code "73") (name "unconnected-(U$1-PD5-Pad22)") (class "Default")
      (node (ref "U$1") (pin "22") (pinfunction "PD5_22") (pintype "bidirectional"))
    )
    (net (code "74") (name "unconnected-(U$1-PF0(ADC0)-Pad41)") (class "Default")
      (node (ref "U$1") (pin "41") (pinfunction "PF0(ADC0)_41") (pintype "bidirectional"))
    )
    (net (code "75") (name "unconnected-(U$1-PF1(ADC1)-Pad40)") (class "Default")
      (node (ref "U$1") (pin "40") (pinfunction "PF1(ADC1)_40") (pintype "bidirectional"))
    )
    (net (code "76") (name "unconnected-(U$1-PF4(ADC4)-Pad39)") (class "Default")
      (node (ref "U$1") (pin "39") (pinfunction "PF4(ADC4)_39") (pintype "bidirectional"))
    )
    (net (code "77") (name "unconnected-(U$1-PF5(ADC5)-Pad38)") (class "Default")
      (node (ref "U$1") (pin "38") (pinfunction "PF5(ADC5)_38") (pintype "bidirectional"))
    )
    (net (code "78") (name "unconnected-(U$2-DRV-Pad22)") (class "Default")
      (node (ref "U$2") (pin "22") (pinfunction "DRV_22") (pintype "bidirectional"))
    )
    (net (code "79") (name "unconnected-(U$2-LED1-Pad23)") (class "Default")
      (node (ref "U$2") (pin "23") (pinfunction "LED1_23") (pintype "bidirectional"))
    )
    (net (code "80") (name "unconnected-(U$2-LED2-Pad24)") (class "Default")
      (node (ref "U$2") (pin "24") (pinfunction "LED2_24") (pintype "bidirectional"))
    )
    (net (code "81") (name "unconnected-(U$2-PWRJ-Pad25)") (class "Default")
      (node (ref "U$2") (pin "25") (pinfunction "PWRJ_25") (pintype "bidirectional"))
    )
    (net (code "82") (name "unconnected-(U$2-TESTJ-Pad27)") (class "Default")
      (node (ref "U$2") (pin "27") (pinfunction "TESTJ_27") (pintype "bidirectional"))
    )
  )
)
